# 36-ETHERNET_PHY_CLOCK_GENERATOR.net
KiCad netlist of a schematic drawn in Altium Designer
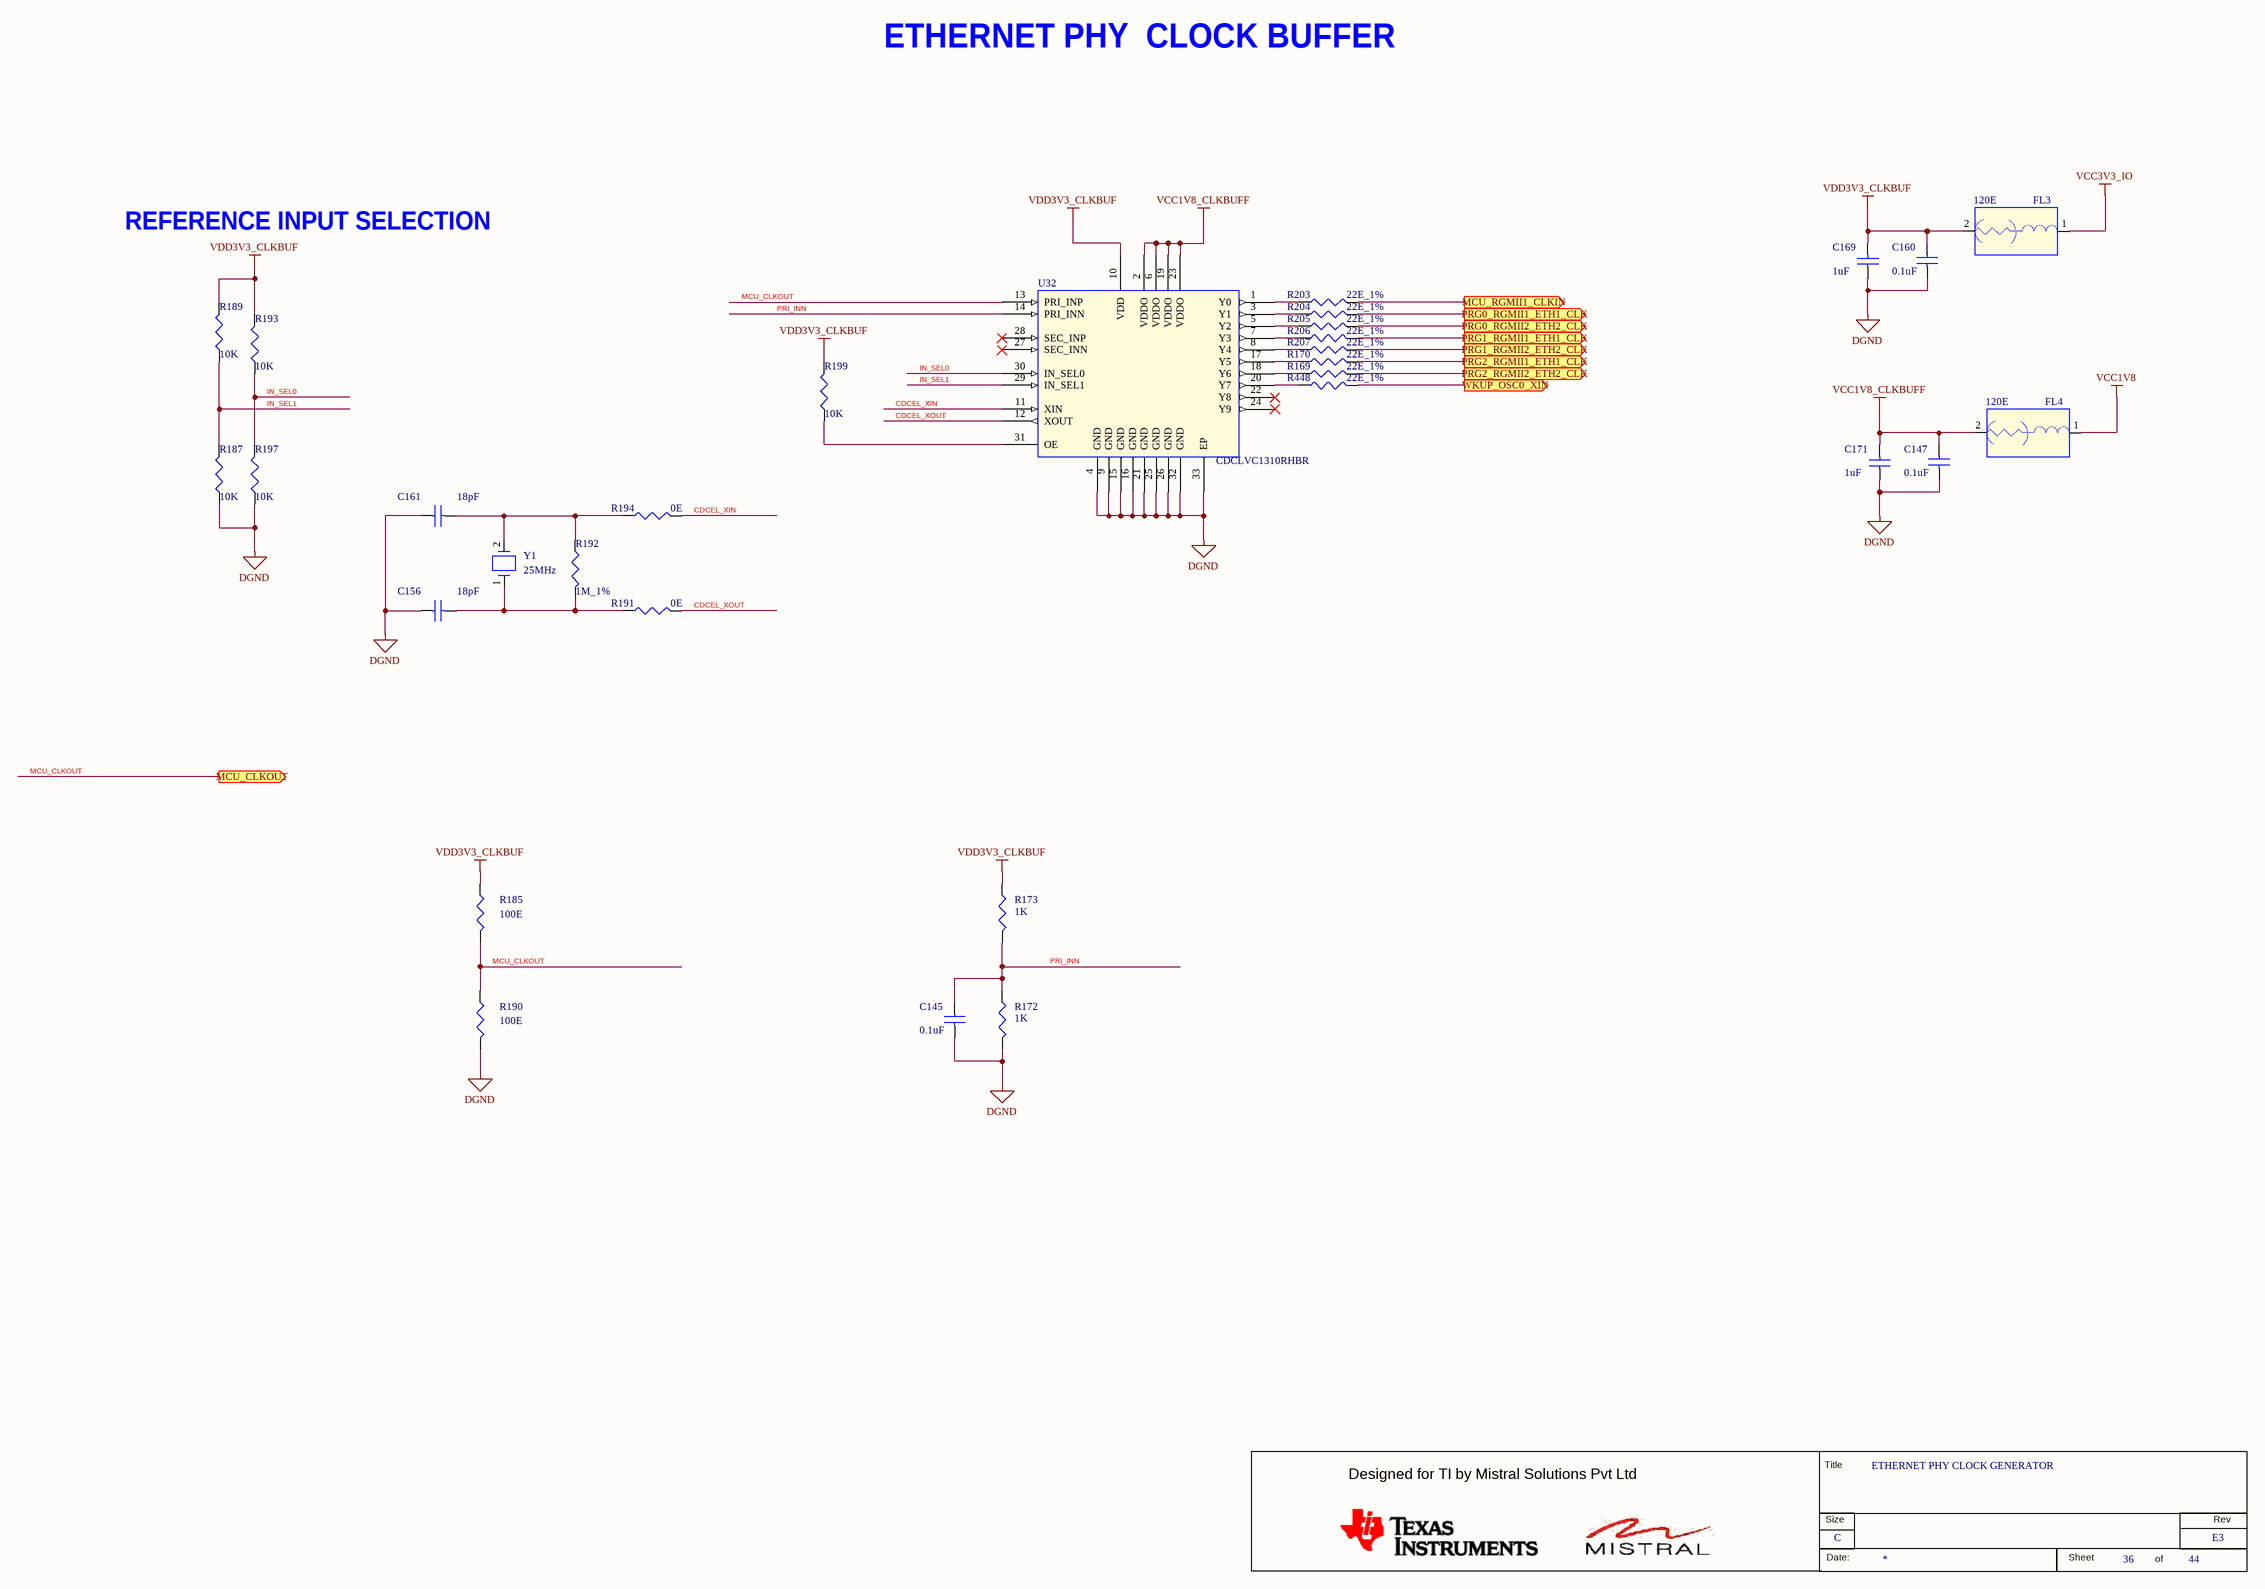
[diagram p0: 36-ETHERNET PHY CLOCK GENERATOR.SchDoc]

(export (version "E")
  (design (tool "Eeschema 10.0.6"))
  (components
    (comp (ref "C145")
      (value "0.1uF")
      (footprint "CAP0201_0-5")
      (description "CAP CERAMIC 0.1uF 16V 10% X5R 0201")
      (fields
        (field (name "MISTRAL PART NO") "120009030072-R")
        (field (name "MFR_PART_NUMBER") "GRM033R61C104KE84J")
      )
      (libsource (lib "*") (part "CAP_Dup5"))
    )
    (comp (ref "C147")
      (value "0.1uF")
      (footprint "CAP0201_0-5")
      (description "CAP CERAMIC 0.1uF 16V 10% X5R 0201")
      (fields
        (field (name "MISTRAL PART NO") "120009030072-R")
        (field (name "MFR_PART_NUMBER") "GRM033R61C104KE84J")
      )
      (libsource (lib "*") (part "CAP_Dup5"))
    )
    (comp (ref "C156")
      (value "18pF")
      (footprint "CAP0402_0-75")
      (description "CAP CERAMIC 18pF 50V 5% C0G(NP0) 0402")
      (fields (field (name "DISTRIBUTOR_PART_NUMBER") "490-5858-1-ND") (field (name "VOLTAGE") "50V"))
      (libsource (lib "*") (part "CAP_Dup5"))
    )
    (comp (ref "C160")
      (value "0.1uF")
      (footprint "CAP0201_0-5")
      (description "CAP CERAMIC 0.1uF 16V 10% X5R 0201")
      (fields (field (name "DISTRIBUTOR_PART_NUMBER") "490-16742-1-ND") (field (name "VOLTAGE") "16V"))
      (libsource (lib "*") (part "CAP_Dup5"))
    )
    (comp (ref "C161")
      (value "18pF")
      (footprint "CAP0402_0-75")
      (description "CAP CERAMIC 18pF 50V 5% C0G(NP0) 0402")
      (fields
        (field (name "MISTRAL PART NO") "120014050002-R")
        (field (name "MFR_PART_NUMBER") "GRM1555C1H180JA01D")
      )
      (libsource (lib "*") (part "CAP_Dup5"))
    )
    (comp (ref "C169")
      (value "1uF")
      (footprint "CAP0402_0-75")
      (description "CAP CERAMIC 1uF 16V 20% X5R 0402")
      (fields
        (field (name "MISTRAL PART NO") "120018020006-R")
        (field (name "MFR_PART_NUMBER") "EMK105BJ105MV-F")
      )
      (libsource (lib "*") (part "CAP_Dup5"))
    )
    (comp (ref "C171")
      (value "1uF")
      (footprint "CAP0402_0-75")
      (description "CAP CERAMIC 1uF 16V 20% X5R 0402")
      (fields (field (name "DISTRIBUTOR_PART_NUMBER") "587-5514-1-ND") (field (name "VOLTAGE") "16V"))
      (libsource (lib "*") (part "CAP_Dup5"))
    )
    (comp (ref "FL3")
      (value "120E")
      (footprint "EMIFIL_BLM15A_0402_0-6")
      (description "FERRITE CHIP 120E 1.3A 0402")
      (fields
        (field (name "MISTRAL PART NO") "130012030043-R")
        (field (name "MFR_PART_NUMBER") "BLM15PD121SN1")
      )
      (libsource (lib "*") (part "EMIFILTER_IND"))
    )
    (comp (ref "FL4")
      (value "120E")
      (footprint "EMIFIL_BLM15A_0402_0-6")
      (description "FERRITE CHIP 120E 1.3A 0402")
      (fields (field (name "DISTRIBUTOR_PART_NUMBER") "490-5203-1-ND") (field (name "VOLTAGE") "NA"))
      (libsource (lib "*") (part "EMIFILTER_IND"))
    )
    (comp (ref "R169")
      (value "22E_1%")
      (footprint "RES0402")
      (description "RES 22E 1/16W 1% 0402")
      (fields
        (field (name "CUST_PART_NUMBER") "4700-80047E")
        (field (name "DISTRIBUTOR_PART_NUMBER") "311-22.0LRCT-ND")
      )
      (libsource (lib "*") (part "RESISTOR_Dup4"))
    )
    (comp (ref "R170")
      (value "22E_1%")
      (footprint "RES0402")
      (description "RES 22E 1/16W 1% 0402")
      (fields
        (field (name "MISTRAL PART NO") "110009090004-P")
        (field (name "MFR_PART_NUMBER") "RC0402FR-0722RL")
      )
      (libsource (lib "*") (part "RESISTOR_Dup4"))
    )
    (comp (ref "R172")
      (value "1K")
      (footprint "RES0201")
      (description "RES 1K 1/20W 5% 0201")
      (fields
        (field (name "MISTRAL PART NO") "110015080014-R")
        (field (name "MFR_PART_NUMBER") "CRCW02011K00FKED")
      )
      (libsource (lib "*") (part "RESISTOR_Dup5"))
    )
    (comp (ref "R173")
      (value "1K")
      (footprint "RES0201")
      (description "RES 1K 1/20W 5% 0201")
      (fields
        (field (name "MISTRAL PART NO") "110015080014-R")
        (field (name "MFR_PART_NUMBER") "CRCW02011K00FKED")
      )
      (libsource (lib "*") (part "RESISTOR_Dup5"))
    )
    (comp (ref "R185")
      (value "100E")
      (footprint "RES0402_0-5")
      (description "RES 100E 1/16W 5% 0402")
      (fields
        (field (name "MISTRAL PART NO") "110009030164-R")
        (field (name "MFR_PART_NUMBER") "CRCW0402100RJNED")
      )
      (libsource (lib "*") (part "RESISTOR_Dup5"))
    )
    (comp (ref "R187")
      (value "10K")
      (footprint "RES0402_0-5")
      (description "RES 10K 1/16W 5% 0402")
      (fields
        (field (name "MISTRAL PART NO") "110009030208-R")
        (field (name "MFR_PART_NUMBER") "RC0402JR-0710KL")
      )
      (libsource (lib "*") (part "RESISTOR_Dup5"))
    )
    (comp (ref "R189")
      (value "10K")
      (footprint "RES0402_0-5")
      (description "RES 10K 1/16W 5% 0402")
      (fields (field (name "DISTRIBUTOR_PART_NUMBER") "311-10KJRCT-ND") (field (name "VOLTAGE") "NA"))
      (libsource (lib "*") (part "RESISTOR_Dup5"))
    )
    (comp (ref "R190")
      (value "100E")
      (footprint "RES0402_0-5")
      (description "RES 100E 1/16W 5% 0402")
      (fields
        (field (name "MISTRAL PART NO") "110009030164-R")
        (field (name "MFR_PART_NUMBER") "CRCW0402100RJNED")
      )
      (libsource (lib "*") (part "RESISTOR_Dup5"))
    )
    (comp (ref "R191")
      (value "0E")
      (footprint "RES0402_0-5")
      (description "RES 0E 1/16W 0402")
      (fields (field (name "DISTRIBUTOR_PART_NUMBER") "541-0.0JCT-ND") (field (name "VOLTAGE") "NA"))
      (libsource (lib "*") (part "RESISTOR_Dup4"))
    )
    (comp (ref "R192")
      (value "1M_1%")
      (footprint "RES0402")
      (description "RES 1M 1/16W 1% 0402")
      (fields
        (field (name "MISTRAL PART NO") "110014060045-R")
        (field (name "MFR_PART_NUMBER") "RMCF0402FT1M00")
      )
      (libsource (lib "*") (part "RESISTOR_Dup5"))
    )
    (comp (ref "R193")
      (value "10K")
      (footprint "RES0402_0-5")
      (description "RES 10K 1/16W 5% 0402")
      (fields
        (field (name "MISTRAL PART NO") "110009030208-R")
        (field (name "MFR_PART_NUMBER") "RC0402JR-0710KL")
      )
      (libsource (lib "*") (part "RESISTOR_Dup5"))
    )
    (comp (ref "R194")
      (value "0E")
      (footprint "RES0402_0-5")
      (description "RES 0E 1/16W 0402")
      (fields
        (field (name "MISTRAL PART NO") "110010080019-P")
        (field (name "MFR_PART_NUMBER") "CRCW04020000Z0ED")
      )
      (libsource (lib "*") (part "RESISTOR_Dup4"))
    )
    (comp (ref "R197")
      (value "10K")
      (footprint "RES0402_0-5")
      (description "RES 10K 1/16W 5% 0402")
      (fields (field (name "DISTRIBUTOR_PART_NUMBER") "311-10KJRCT-ND") (field (name "VOLTAGE") "NA"))
      (libsource (lib "*") (part "RESISTOR_Dup5"))
    )
    (comp (ref "R199")
      (value "10K")
      (footprint "RES0402_0-5")
      (description "RES 10K 1/16W 5% 0402")
      (fields
        (field (name "MISTRAL PART NO") "110009030208-R")
        (field (name "MFR_PART_NUMBER") "RC0402JR-0710KL")
      )
      (libsource (lib "*") (part "RESISTOR_Dup5"))
    )
    (comp (ref "R203")
      (value "22E_1%")
      (footprint "RES0402")
      (description "RES 22E 1/16W 1% 0402")
      (fields
        (field (name "CUST_PART_NUMBER") "4700-80047E")
        (field (name "DISTRIBUTOR_PART_NUMBER") "311-22.0LRCT-ND")
      )
      (libsource (lib "*") (part "RESISTOR_Dup4"))
    )
    (comp (ref "R204")
      (value "22E_1%")
      (footprint "RES0402")
      (description "RES 22E 1/16W 1% 0402")
      (fields
        (field (name "MISTRAL PART NO") "110009090004-P")
        (field (name "MFR_PART_NUMBER") "RC0402FR-0722RL")
      )
      (libsource (lib "*") (part "RESISTOR_Dup4"))
    )
    (comp (ref "R205")
      (value "22E_1%")
      (footprint "RES0402")
      (description "RES 22E 1/16W 1% 0402")
      (fields
        (field (name "CUST_PART_NUMBER") "4700-80047E")
        (field (name "DISTRIBUTOR_PART_NUMBER") "311-22.0LRCT-ND")
      )
      (libsource (lib "*") (part "RESISTOR_Dup4"))
    )
    (comp (ref "R206")
      (value "22E_1%")
      (footprint "RES0402")
      (description "RES 22E 1/16W 1% 0402")
      (fields
        (field (name "MISTRAL PART NO") "110009090004-P")
        (field (name "MFR_PART_NUMBER") "RC0402FR-0722RL")
      )
      (libsource (lib "*") (part "RESISTOR_Dup4"))
    )
    (comp (ref "R207")
      (value "22E_1%")
      (footprint "RES0402")
      (description "RES 22E 1/16W 1% 0402")
      (fields
        (field (name "CUST_PART_NUMBER") "4700-80047E")
        (field (name "DISTRIBUTOR_PART_NUMBER") "311-22.0LRCT-ND")
      )
      (libsource (lib "*") (part "RESISTOR_Dup4"))
    )
    (comp (ref "R448")
      (value "22E_1%")
      (footprint "RES0402")
      (description "RES 22E 1/16W 1% 0402")
      (fields
        (field (name "CUST_PART_NUMBER") "4700-80047E")
        (field (name "DISTRIBUTOR_PART_NUMBER") "311-22.0LRCT-ND")
      )
      (libsource (lib "*") (part "RESISTOR_Dup4"))
    )
    (comp (ref "U32")
      (value "CDCLVC1310RHBR")
      (footprint "QFN32_19-68_200X200_1")
      (description "IC LOW JITTER,LOW POWER CLK BUFFER LEVEL TRANSLATOR VQFN32")
      (fields (field (name "DISTRIBUTOR_PART_NUMBER") "296-30105-1-ND") (field (name "VOLTAGE") "NA"))
      (libsource (lib "*") (part "CDCLVC1310RHBR_VQFN32"))
    )
    (comp (ref "Y1")
      (value "25MHz")
      (footprint "XTAL_ABM3_210X130_SMD")
      (description "CRY 25MHz SMD")
      (fields (field (name "DISTRIBUTOR_PART_NUMBER") "535-10645-1-ND") (field (name "VOLTAGE") "NA"))
      (libsource (lib "*") (part "CRY"))
    )
  )
  (nets
    (net (code "1") (name "/CDCEL_XIN") (class "Default")
      (node (ref "R194") (pin "2") (pinfunction "2_2") (pintype "passive"))
      (node (ref "U32") (pin "11") (pinfunction "XIN_11") (pintype "input"))
    )
    (net (code "2") (name "/CDCEL_XOUT") (class "Default")
      (node (ref "R191") (pin "2") (pinfunction "2_2") (pintype "passive"))
      (node (ref "U32") (pin "12") (pinfunction "XOUT_12") (pintype "output"))
    )
    (net (code "3") (name "/IN_SEL0") (class "Default")
      (node (ref "R193") (pin "1") (pinfunction "1_1") (pintype "passive"))
      (node (ref "R197") (pin "2") (pinfunction "2_2") (pintype "passive"))
      (node (ref "U32") (pin "30") (pinfunction "IN_SEL0_30") (pintype "input"))
    )
    (net (code "4") (name "/IN_SEL1") (class "Default")
      (node (ref "R187") (pin "2") (pinfunction "2_2") (pintype "passive"))
      (node (ref "R189") (pin "1") (pinfunction "1_1") (pintype "passive"))
      (node (ref "U32") (pin "29") (pinfunction "IN_SEL1_29") (pintype "input"))
    )
    (net (code "5") (name "/MCU_CLKOUT") (class "Default")
      (node (ref "R185") (pin "2") (pinfunction "2_2") (pintype "passive"))
      (node (ref "R190") (pin "1") (pinfunction "1_1") (pintype "passive"))
      (node (ref "U32") (pin "13") (pinfunction "PRI_INP_13") (pintype "input"))
    )
    (net (code "6") (name "/MCU_RGMII1_CLKIN") (class "Default")
      (node (ref "R203") (pin "2") (pinfunction "2_2") (pintype "passive"))
    )
    (net (code "7") (name "/PRG0_RGMII1_ETH1_CLK") (class "Default")
      (node (ref "R204") (pin "2") (pinfunction "2_2") (pintype "passive"))
    )
    (net (code "8") (name "/PRG0_RGMII2_ETH2_CLK") (class "Default")
      (node (ref "R205") (pin "2") (pinfunction "2_2") (pintype "passive"))
    )
    (net (code "9") (name "/PRG1_RGMII1_ETH1_CLK") (class "Default")
      (node (ref "R206") (pin "2") (pinfunction "2_2") (pintype "passive"))
    )
    (net (code "10") (name "/PRG1_RGMII2_ETH2_CLK") (class "Default")
      (node (ref "R207") (pin "2") (pinfunction "2_2") (pintype "passive"))
    )
    (net (code "11") (name "/PRG2_RGMII1_ETH1_CLK") (class "Default")
      (node (ref "R170") (pin "2") (pinfunction "2_2") (pintype "passive"))
    )
    (net (code "12") (name "/PRG2_RGMII2_ETH2_CLK") (class "Default")
      (node (ref "R169") (pin "2") (pinfunction "2_2") (pintype "passive"))
    )
    (net (code "13") (name "/PRI_INN") (class "Default")
      (node (ref "C145") (pin "1") (pinfunction "1_1") (pintype "passive"))
      (node (ref "R172") (pin "1") (pinfunction "1_1") (pintype "passive"))
      (node (ref "R173") (pin "2") (pinfunction "2_2") (pintype "passive"))
      (node (ref "U32") (pin "14") (pinfunction "PRI_INN_14") (pintype "input"))
    )
    (net (code "14") (name "/WKUP_OSC0_XIN") (class "Default")
      (node (ref "R448") (pin "2") (pinfunction "2_2") (pintype "passive"))
    )
    (net (code "15") (name "DGND") (class "Default")
      (node (ref "C145") (pin "2") (pinfunction "2_2") (pintype "passive"))
      (node (ref "C147") (pin "2") (pinfunction "2_2") (pintype "passive"))
      (node (ref "C156") (pin "1") (pinfunction "1_1") (pintype "passive"))
      (node (ref "C160") (pin "2") (pinfunction "2_2") (pintype "passive"))
      (node (ref "C161") (pin "1") (pinfunction "1_1") (pintype "passive"))
      (node (ref "C169") (pin "1") (pinfunction "1_1") (pintype "passive"))
      (node (ref "C171") (pin "1") (pinfunction "1_1") (pintype "passive"))
      (node (ref "R172") (pin "2") (pinfunction "2_2") (pintype "passive"))
      (node (ref "R187") (pin "1") (pinfunction "1_1") (pintype "passive"))
      (node (ref "R190") (pin "2") (pinfunction "2_2") (pintype "passive"))
      (node (ref "R197") (pin "1") (pinfunction "1_1") (pintype "passive"))
      (node (ref "U32") (pin "15") (pinfunction "GND_15") (pintype "power_in"))
      (node (ref "U32") (pin "16") (pinfunction "GND_16") (pintype "power_in"))
      (node (ref "U32") (pin "21") (pinfunction "GND_21") (pintype "power_in"))
      (node (ref "U32") (pin "25") (pinfunction "GND_25") (pintype "power_in"))
      (node (ref "U32") (pin "26") (pinfunction "GND_26") (pintype "power_in"))
      (node (ref "U32") (pin "32") (pinfunction "GND_32") (pintype "power_in"))
      (node (ref "U32") (pin "33") (pinfunction "EP_33") (pintype "power_in"))
      (node (ref "U32") (pin "4") (pinfunction "GND_4") (pintype "power_in"))
      (node (ref "U32") (pin "9") (pinfunction "GND_9") (pintype "power_in"))
    )
    (net (code "16") (name "Net-(C156-Pad2)") (class "Default")
      (node (ref "C156") (pin "2") (pinfunction "2_2") (pintype "passive"))
      (node (ref "R191") (pin "1") (pinfunction "1_1") (pintype "passive"))
      (node (ref "R192") (pin "2") (pinfunction "2_2") (pintype "passive"))
      (node (ref "Y1") (pin "1") (pinfunction "1_1") (pintype "passive"))
    )
    (net (code "17") (name "Net-(C161-Pad2)") (class "Default")
      (node (ref "C161") (pin "2") (pinfunction "2_2") (pintype "passive"))
      (node (ref "R192") (pin "1") (pinfunction "1_1") (pintype "passive"))
      (node (ref "R194") (pin "1") (pinfunction "1_1") (pintype "passive"))
      (node (ref "Y1") (pin "2") (pinfunction "2_2") (pintype "passive"))
    )
    (net (code "18") (name "Net-(U32-OE)") (class "Default")
      (node (ref "R199") (pin "1") (pinfunction "1_1") (pintype "passive"))
      (node (ref "U32") (pin "31") (pinfunction "OE_31") (pintype "passive"))
    )
    (net (code "19") (name "Net-(U32-Y0)") (class "Default")
      (node (ref "R203") (pin "1") (pinfunction "1_1") (pintype "passive"))
      (node (ref "U32") (pin "1") (pinfunction "Y0_1") (pintype "output"))
    )
    (net (code "20") (name "Net-(U32-Y1)") (class "Default")
      (node (ref "R204") (pin "1") (pinfunction "1_1") (pintype "passive"))
      (node (ref "U32") (pin "3") (pinfunction "Y1_3") (pintype "output"))
    )
    (net (code "21") (name "Net-(U32-Y2)") (class "Default")
      (node (ref "R205") (pin "1") (pinfunction "1_1") (pintype "passive"))
      (node (ref "U32") (pin "5") (pinfunction "Y2_5") (pintype "output"))
    )
    (net (code "22") (name "Net-(U32-Y3)") (class "Default")
      (node (ref "R206") (pin "1") (pinfunction "1_1") (pintype "passive"))
      (node (ref "U32") (pin "7") (pinfunction "Y3_7") (pintype "output"))
    )
    (net (code "23") (name "Net-(U32-Y4)") (class "Default")
      (node (ref "R207") (pin "1") (pinfunction "1_1") (pintype "passive"))
      (node (ref "U32") (pin "8") (pinfunction "Y4_8") (pintype "output"))
    )
    (net (code "24") (name "Net-(U32-Y5)") (class "Default")
      (node (ref "R170") (pin "1") (pinfunction "1_1") (pintype "passive"))
      (node (ref "U32") (pin "17") (pinfunction "Y5_17") (pintype "output"))
    )
    (net (code "25") (name "Net-(U32-Y6)") (class "Default")
      (node (ref "R169") (pin "1") (pinfunction "1_1") (pintype "passive"))
      (node (ref "U32") (pin "18") (pinfunction "Y6_18") (pintype "output"))
    )
    (net (code "26") (name "Net-(U32-Y7)") (class "Default")
      (node (ref "R448") (pin "1") (pinfunction "1_1") (pintype "passive"))
      (node (ref "U32") (pin "20") (pinfunction "Y7_20") (pintype "output"))
    )
    (net (code "27") (name "VCC1V8") (class "Default")
      (node (ref "FL4") (pin "1") (pinfunction "1_1") (pintype "passive"))
    )
    (net (code "28") (name "VCC1V8_CLKBUFF") (class "Default")
      (node (ref "C147") (pin "1") (pinfunction "1_1") (pintype "passive"))
      (node (ref "C171") (pin "2") (pinfunction "2_2") (pintype "passive"))
      (node (ref "FL4") (pin "2") (pinfunction "2_2") (pintype "passive"))
      (node (ref "U32") (pin "19") (pinfunction "VDDO_19") (pintype "power_in"))
      (node (ref "U32") (pin "2") (pinfunction "VDDO_2") (pintype "power_in"))
      (node (ref "U32") (pin "23") (pinfunction "VDDO_23") (pintype "power_in"))
      (node (ref "U32") (pin "6") (pinfunction "VDDO_6") (pintype "power_in"))
    )
    (net (code "29") (name "VCC3V3_IO") (class "Default")
      (node (ref "FL3") (pin "1") (pinfunction "1_1") (pintype "passive"))
    )
    (net (code "30") (name "VDD3V3_CLKBUF") (class "Default")
      (node (ref "C160") (pin "1") (pinfunction "1_1") (pintype "passive"))
      (node (ref "C169") (pin "2") (pinfunction "2_2") (pintype "passive"))
      (node (ref "FL3") (pin "2") (pinfunction "2_2") (pintype "passive"))
      (node (ref "R173") (pin "1") (pinfunction "1_1") (pintype "passive"))
      (node (ref "R185") (pin "1") (pinfunction "1_1") (pintype "passive"))
      (node (ref "R189") (pin "2") (pinfunction "2_2") (pintype "passive"))
      (node (ref "R193") (pin "2") (pinfunction "2_2") (pintype "passive"))
      (node (ref "R199") (pin "2") (pinfunction "2_2") (pintype "passive"))
      (node (ref "U32") (pin "10") (pinfunction "VDD_10") (pintype "power_in"))
    )
    (net (code "31") (name "unconnected-(U32-SEC_INN-Pad27)") (class "Default")
      (node (ref "U32") (pin "27") (pinfunction "SEC_INN_27") (pintype "input+no_connect"))
    )
    (net (code "32") (name "unconnected-(U32-SEC_INP-Pad28)") (class "Default")
      (node (ref "U32") (pin "28") (pinfunction "SEC_INP_28") (pintype "input+no_connect"))
    )
    (net (code "33") (name "unconnected-(U32-Y8-Pad22)") (class "Default")
      (node (ref "U32") (pin "22") (pinfunction "Y8_22") (pintype "output+no_connect"))
    )
    (net (code "34") (name "unconnected-(U32-Y9-Pad24)") (class "Default")
      (node (ref "U32") (pin "24") (pinfunction "Y9_24") (pintype "output+no_connect"))
    )
  )
)
